# M707C.net
KiCad netlist of a schematic drawn in EAGLE
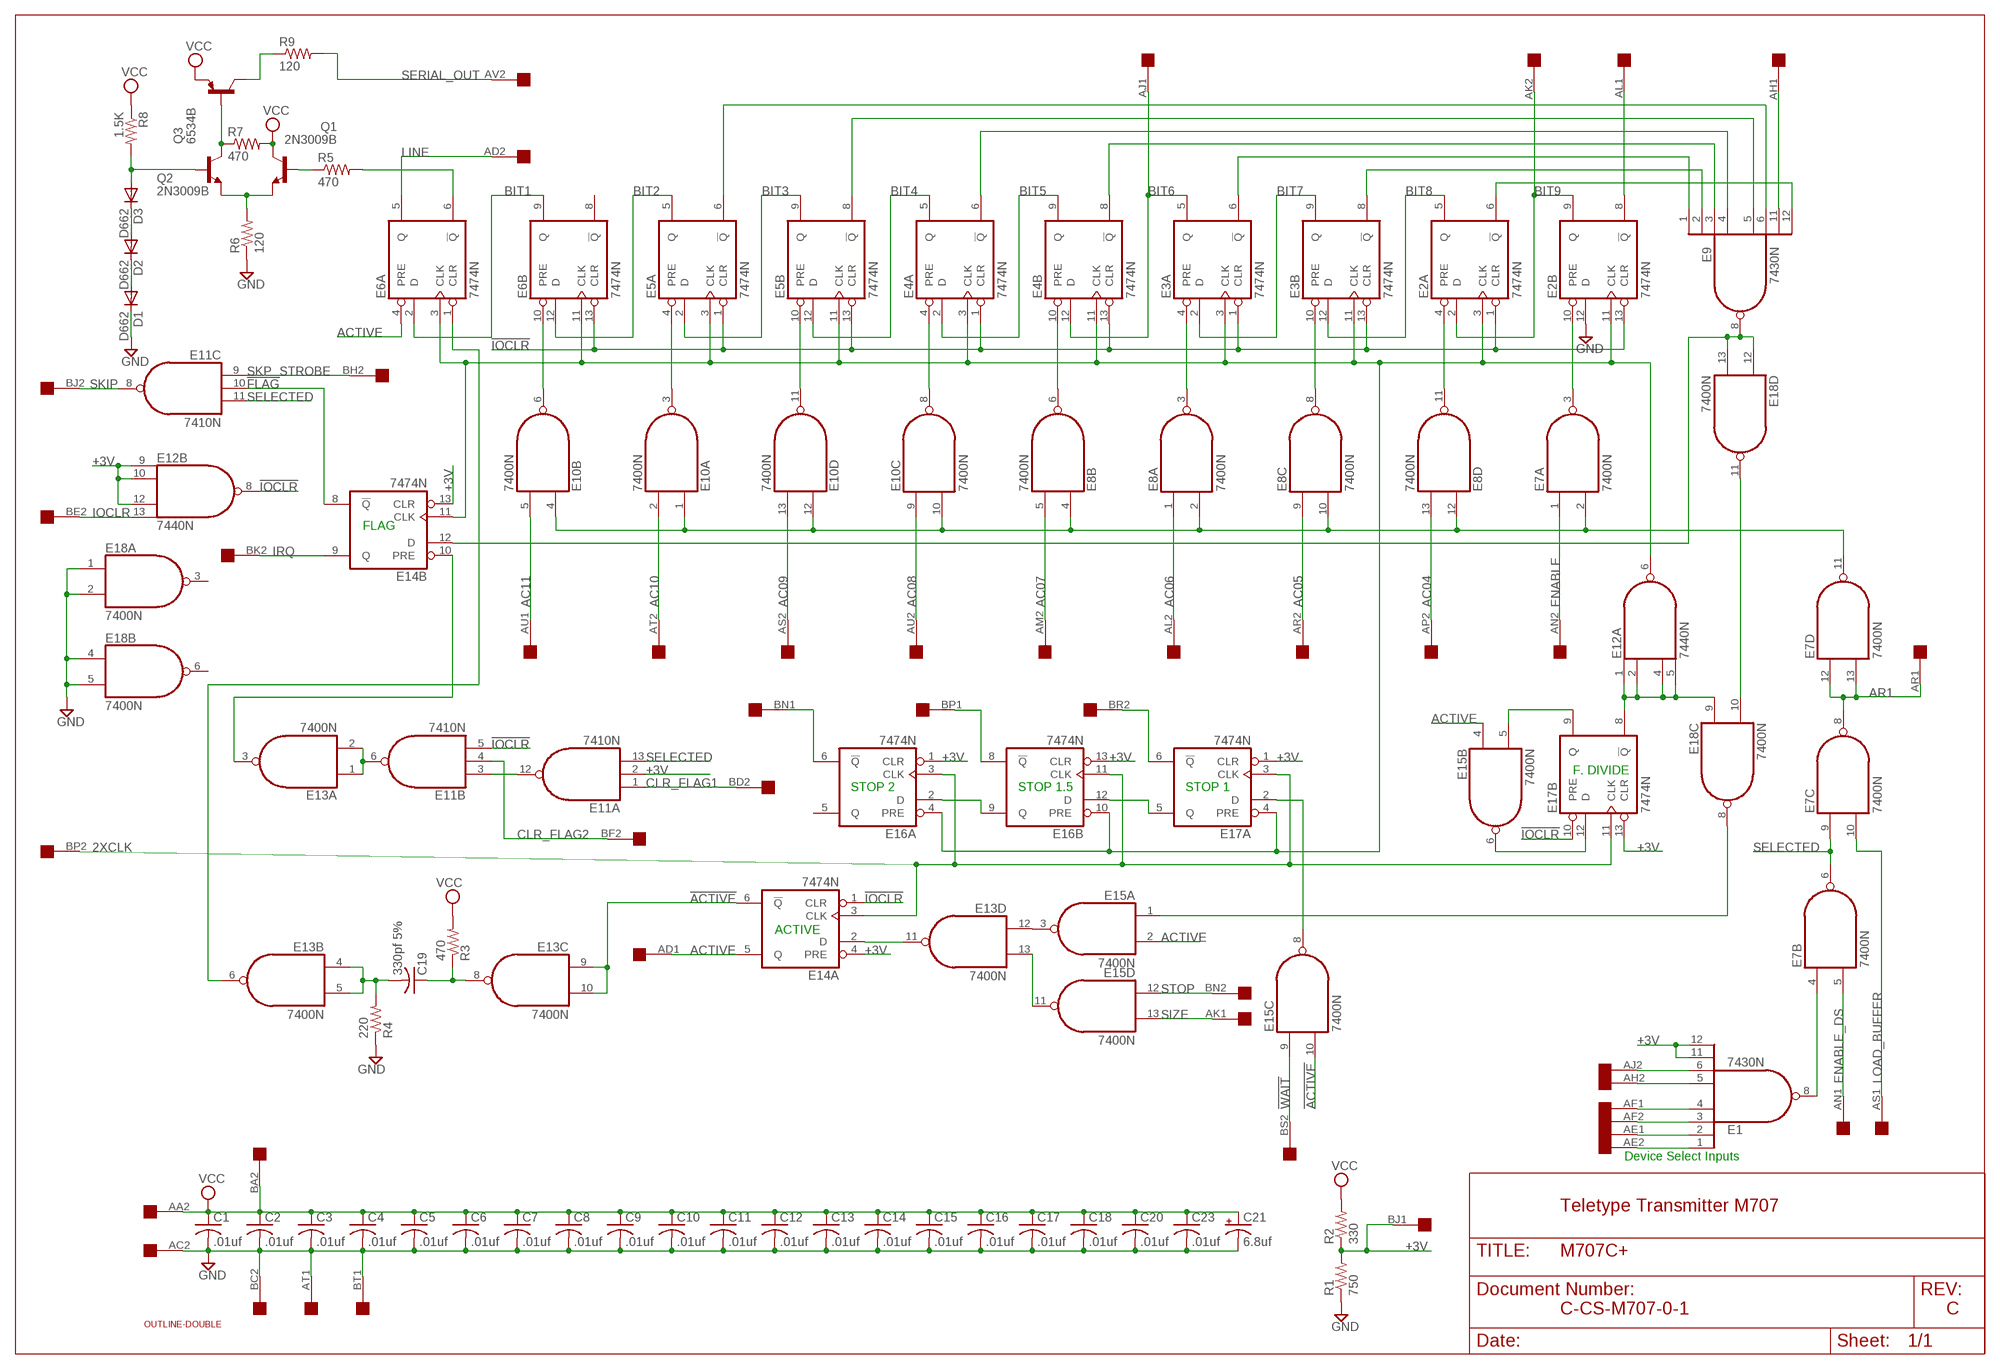
[diagram p0: schematic, sheet 1]

(export (version "E")
  (design (tool "Eeschema 10.0.6"))
  (components
    (comp (ref "C1")
      (value ".01uf")
      (footprint "eagle-import:C075-032X103")
      (libsource (lib "eagle-import") (part "C-US075-032X103"))
    )
    (comp (ref "C2")
      (value ".01uf")
      (footprint "eagle-import:C075-032X103")
      (libsource (lib "eagle-import") (part "C-US075-032X103"))
    )
    (comp (ref "C3")
      (value ".01uf")
      (footprint "eagle-import:C075-032X103")
      (libsource (lib "eagle-import") (part "C-US075-032X103"))
    )
    (comp (ref "C4")
      (value ".01uf")
      (footprint "eagle-import:C075-032X103")
      (libsource (lib "eagle-import") (part "C-US075-032X103"))
    )
    (comp (ref "C5")
      (value ".01uf")
      (footprint "eagle-import:C075-032X103")
      (libsource (lib "eagle-import") (part "C-US075-032X103"))
    )
    (comp (ref "C6")
      (value ".01uf")
      (footprint "eagle-import:C075-032X103")
      (libsource (lib "eagle-import") (part "C-US075-032X103"))
    )
    (comp (ref "C7")
      (value ".01uf")
      (footprint "eagle-import:C075-032X103")
      (libsource (lib "eagle-import") (part "C-US075-032X103"))
    )
    (comp (ref "C8")
      (value ".01uf")
      (footprint "eagle-import:C075-032X103")
      (libsource (lib "eagle-import") (part "C-US075-032X103"))
    )
    (comp (ref "C9")
      (value ".01uf")
      (footprint "eagle-import:C075-032X103")
      (libsource (lib "eagle-import") (part "C-US075-032X103"))
    )
    (comp (ref "C10")
      (value ".01uf")
      (footprint "eagle-import:C075-032X103")
      (libsource (lib "eagle-import") (part "C-US075-032X103"))
    )
    (comp (ref "C11")
      (value ".01uf")
      (footprint "eagle-import:C075-032X103")
      (libsource (lib "eagle-import") (part "C-US075-032X103"))
    )
    (comp (ref "C12")
      (value ".01uf")
      (footprint "eagle-import:C075-032X103")
      (libsource (lib "eagle-import") (part "C-US075-032X103"))
    )
    (comp (ref "C13")
      (value ".01uf")
      (footprint "eagle-import:C075-032X103")
      (libsource (lib "eagle-import") (part "C-US075-032X103"))
    )
    (comp (ref "C14")
      (value ".01uf")
      (footprint "eagle-import:C075-032X103")
      (libsource (lib "eagle-import") (part "C-US075-032X103"))
    )
    (comp (ref "C15")
      (value ".01uf")
      (footprint "eagle-import:C075-032X103")
      (libsource (lib "eagle-import") (part "C-US075-032X103"))
    )
    (comp (ref "C16")
      (value ".01uf")
      (footprint "eagle-import:C075-032X103")
      (libsource (lib "eagle-import") (part "C-US075-032X103"))
    )
    (comp (ref "C17")
      (value ".01uf")
      (footprint "eagle-import:C075-032X103")
      (libsource (lib "eagle-import") (part "C-US075-032X103"))
    )
    (comp (ref "C18")
      (value ".01uf")
      (footprint "eagle-import:C075-032X103")
      (libsource (lib "eagle-import") (part "C-US075-032X103"))
    )
    (comp (ref "C19")
      (value "330pf 5%")
      (footprint "eagle-import:C150-054X183")
      (libsource (lib "eagle-import") (part "C-US150-054X183"))
    )
    (comp (ref "C20")
      (value ".01uf")
      (footprint "eagle-import:C075-032X103")
      (libsource (lib "eagle-import") (part "C-US075-032X103"))
    )
    (comp (ref "C21")
      (value "6.8uf")
      (footprint "eagle-import:E15-5")
      (libsource (lib "eagle-import") (part "CPOL-USE15-5AXIAL"))
    )
    (comp (ref "C23")
      (value ".01uf")
      (footprint "eagle-import:C075-032X103")
      (libsource (lib "eagle-import") (part "C-US075-032X103"))
    )
    (comp (ref "D1")
      (value "D662")
      (footprint "eagle-import:SOD61B")
      (libsource (lib "eagle-import") (part "BY609"))
    )
    (comp (ref "D2")
      (value "D662")
      (footprint "eagle-import:SOD61B")
      (libsource (lib "eagle-import") (part "BY609"))
    )
    (comp (ref "D3")
      (value "D662")
      (footprint "eagle-import:SOD61B")
      (libsource (lib "eagle-import") (part "BY609"))
    )
    (comp (ref "E1")
      (value "7430N")
      (footprint "eagle-import:DIL14")
      (libsource (lib "eagle-import") (part "7430N"))
    )
    (comp (ref "E2")
      (value "7474N")
      (footprint "eagle-import:DIL14")
      (libsource (lib "eagle-import") (part "7474NS"))
    )
    (comp (ref "E3")
      (value "7474N")
      (footprint "eagle-import:DIL14")
      (libsource (lib "eagle-import") (part "7474NS"))
    )
    (comp (ref "E4")
      (value "7474N")
      (footprint "eagle-import:DIL14")
      (libsource (lib "eagle-import") (part "7474NS"))
    )
    (comp (ref "E5")
      (value "7474N")
      (footprint "eagle-import:DIL14")
      (libsource (lib "eagle-import") (part "7474NS"))
    )
    (comp (ref "E6")
      (value "7474N")
      (footprint "eagle-import:DIL14")
      (libsource (lib "eagle-import") (part "7474NS"))
    )
    (comp (ref "E7")
      (value "7400N")
      (footprint "eagle-import:DIL14")
      (libsource (lib "eagle-import") (part "7400N"))
    )
    (comp (ref "E8")
      (value "7400N")
      (footprint "eagle-import:DIL14")
      (libsource (lib "eagle-import") (part "7400N"))
    )
    (comp (ref "E9")
      (value "7430N")
      (footprint "eagle-import:DIL14")
      (libsource (lib "eagle-import") (part "7430N"))
    )
    (comp (ref "E10")
      (value "7400N")
      (footprint "eagle-import:DIL14")
      (libsource (lib "eagle-import") (part "7400N"))
    )
    (comp (ref "E11")
      (value "7410N")
      (footprint "eagle-import:DIL14")
      (libsource (lib "eagle-import") (part "7410N"))
    )
    (comp (ref "E12")
      (value "7440N")
      (footprint "eagle-import:DIL14")
      (libsource (lib "eagle-import") (part "7420NS"))
    )
    (comp (ref "E13")
      (value "7400N")
      (footprint "eagle-import:DIL14")
      (libsource (lib "eagle-import") (part "7400N"))
    )
    (comp (ref "E14")
      (value "7474N")
      (footprint "eagle-import:DIL14")
      (libsource (lib "eagle-import") (part "7474NS"))
    )
    (comp (ref "E15")
      (value "7400N")
      (footprint "eagle-import:DIL14")
      (libsource (lib "eagle-import") (part "7400N"))
    )
    (comp (ref "E16")
      (value "7474N")
      (footprint "eagle-import:DIL14")
      (libsource (lib "eagle-import") (part "7474NS"))
    )
    (comp (ref "E17")
      (value "7474N")
      (footprint "eagle-import:DIL14")
      (libsource (lib "eagle-import") (part "7474NS"))
    )
    (comp (ref "E18")
      (value "7400N")
      (footprint "eagle-import:DIL14")
      (libsource (lib "eagle-import") (part "7400N"))
    )
    (comp (ref "Q1")
      (value "2N3009B")
      (footprint "eagle-import:TO92-CBE")
      (libsource (lib "eagle-import") (part "-NPN-TO92-CBE2N4124"))
    )
    (comp (ref "Q2")
      (value "2N3009B")
      (footprint "eagle-import:TO92-CBE")
      (libsource (lib "eagle-import") (part "-NPN-TO92-CBE2N4124"))
    )
    (comp (ref "Q3")
      (value "6534B")
      (footprint "eagle-import:TO92-CBE")
      (libsource (lib "eagle-import") (part "-PNP-TO92-CBE2N4126"))
    )
    (comp (ref "R1")
      (value "750")
      (footprint "eagle-import:0207_15")
      (libsource (lib "eagle-import") (part "R-US_0207/15"))
    )
    (comp (ref "R2")
      (value "330")
      (footprint "eagle-import:0207_15")
      (libsource (lib "eagle-import") (part "R-US_0207/15"))
    )
    (comp (ref "R3")
      (value "470")
      (footprint "eagle-import:0207_10")
      (libsource (lib "eagle-import") (part "R-US_0207/10"))
    )
    (comp (ref "R4")
      (value "220")
      (footprint "eagle-import:0207_10")
      (libsource (lib "eagle-import") (part "R-US_0207/10"))
    )
    (comp (ref "R5")
      (value "470")
      (footprint "eagle-import:0207_10")
      (libsource (lib "eagle-import") (part "R-US_0207/10"))
    )
    (comp (ref "R6")
      (value "120")
      (footprint "eagle-import:0207_15")
      (libsource (lib "eagle-import") (part "R-US_0207/15"))
    )
    (comp (ref "R7")
      (value "470")
      (footprint "eagle-import:0207_10")
      (libsource (lib "eagle-import") (part "R-US_0207/10"))
    )
    (comp (ref "R8")
      (value "1.5K")
      (footprint "eagle-import:0207_15")
      (libsource (lib "eagle-import") (part "R-US_0207/15"))
    )
    (comp (ref "R9")
      (value "120")
      (footprint "eagle-import:0204_7")
      (libsource (lib "eagle-import") (part "R-US_0204/7"))
    )
    (comp (ref "U$1")
      (value "OUTLINE-DOUBLE")
      (footprint "eagle-import:DOUBLE")
      (libsource (lib "eagle-import") (part "OUTLINE-DOUBLE"))
    )
    (comp (ref "U$2")
      (value "DOUBLE")
      (footprint "eagle-import:EDGE-CON4")
      (libsource (lib "eagle-import") (part "DOUBLE"))
    )
  )
  (nets
    (net (code "1") (name "/+3V") (class "Default")
      (node (ref "E1") (pin "11") (pinfunction "I6_11") (pintype "input"))
      (node (ref "E1") (pin "12") (pinfunction "I7_12") (pintype "input"))
      (node (ref "E11") (pin "2") (pinfunction "I1_2") (pintype "input"))
      (node (ref "E12") (pin "10") (pinfunction "I1_10") (pintype "input"))
      (node (ref "E12") (pin "12") (pinfunction "I2_12") (pintype "input"))
      (node (ref "E12") (pin "9") (pinfunction "I0_9") (pintype "input"))
      (node (ref "E14") (pin "13") (pinfunction "CLR_13") (pintype "input"))
      (node (ref "E14") (pin "4") (pinfunction "PRE_4") (pintype "input"))
      (node (ref "E16") (pin "1") (pinfunction "CLR_1") (pintype "input"))
      (node (ref "E16") (pin "13") (pinfunction "CLR_13") (pintype "input"))
      (node (ref "E17") (pin "1") (pinfunction "CLR_1") (pintype "input"))
      (node (ref "E17") (pin "13") (pinfunction "CLR_13") (pintype "input"))
      (node (ref "R1") (pin "2") (pinfunction "2_2") (pintype "passive"))
      (node (ref "R2") (pin "1") (pinfunction "1_1") (pintype "passive"))
      (node (ref "U$2") (pin "BJ1") (pinfunction "1_BJ1") (pintype "bidirectional"))
    )
    (net (code "2") (name "/2XCLK") (class "Default")
      (node (ref "E14") (pin "3") (pinfunction "CLK_3") (pintype "input"))
      (node (ref "E16") (pin "11") (pinfunction "CLK_11") (pintype "input"))
      (node (ref "E16") (pin "3") (pinfunction "CLK_3") (pintype "input"))
      (node (ref "E17") (pin "11") (pinfunction "CLK_11") (pintype "input"))
      (node (ref "E17") (pin "3") (pinfunction "CLK_3") (pintype "input"))
      (node (ref "U$2") (pin "BP2") (pinfunction "1_BP2") (pintype "bidirectional"))
    )
    (net (code "3") (name "/AC04") (class "Default")
      (node (ref "E8") (pin "13") (pinfunction "I1_13") (pintype "input"))
      (node (ref "U$2") (pin "AP2") (pinfunction "1_AP2") (pintype "bidirectional"))
    )
    (net (code "4") (name "/AC05") (class "Default")
      (node (ref "E8") (pin "9") (pinfunction "I0_9") (pintype "input"))
      (node (ref "U$2") (pin "AR2") (pinfunction "1_AR2") (pintype "bidirectional"))
    )
    (net (code "5") (name "/AC06") (class "Default")
      (node (ref "E8") (pin "1") (pinfunction "I0_1") (pintype "input"))
      (node (ref "U$2") (pin "AL2") (pinfunction "1_AL2") (pintype "bidirectional"))
    )
    (net (code "6") (name "/AC07") (class "Default")
      (node (ref "E8") (pin "5") (pinfunction "I1_5") (pintype "input"))
      (node (ref "U$2") (pin "AM2") (pinfunction "1_AM2") (pintype "bidirectional"))
    )
    (net (code "7") (name "/AC08") (class "Default")
      (node (ref "E10") (pin "9") (pinfunction "I0_9") (pintype "input"))
      (node (ref "U$2") (pin "AU2") (pinfunction "1_AU2") (pintype "bidirectional"))
    )
    (net (code "8") (name "/AC09") (class "Default")
      (node (ref "E10") (pin "13") (pinfunction "I1_13") (pintype "input"))
      (node (ref "U$2") (pin "AS2") (pinfunction "1_AS2") (pintype "bidirectional"))
    )
    (net (code "9") (name "/AC10") (class "Default")
      (node (ref "E10") (pin "2") (pinfunction "I1_2") (pintype "input"))
      (node (ref "U$2") (pin "AT2") (pinfunction "1_AT2") (pintype "bidirectional"))
    )
    (net (code "10") (name "/AC11") (class "Default")
      (node (ref "E10") (pin "5") (pinfunction "I1_5") (pintype "input"))
      (node (ref "U$2") (pin "AU1") (pinfunction "1_AU1") (pintype "bidirectional"))
    )
    (net (code "11") (name "/ACTIVE") (class "Default")
      (node (ref "E14") (pin "5") (pinfunction "Q_5") (pintype "output"))
      (node (ref "E15") (pin "2") (pinfunction "I1_2") (pintype "input"))
      (node (ref "E15") (pin "4") (pinfunction "I0_4") (pintype "input"))
      (node (ref "E6") (pin "4") (pinfunction "PRE_4") (pintype "input"))
      (node (ref "U$2") (pin "AD1") (pinfunction "1_AD1") (pintype "bidirectional"))
    )
    (net (code "12") (name "/AR1") (class "Default")
      (node (ref "E7") (pin "12") (pinfunction "I0_12") (pintype "input"))
      (node (ref "E7") (pin "13") (pinfunction "I1_13") (pintype "input"))
      (node (ref "E7") (pin "8") (pinfunction "O_8") (pintype "output"))
      (node (ref "U$2") (pin "AR1") (pinfunction "1_AR1") (pintype "bidirectional"))
    )
    (net (code "13") (name "/BIT1") (class "Default")
      (node (ref "E6") (pin "2") (pinfunction "D_2") (pintype "input"))
      (node (ref "E6") (pin "9") (pinfunction "Q_9") (pintype "output"))
    )
    (net (code "14") (name "/BIT2") (class "Default")
      (node (ref "E5") (pin "5") (pinfunction "Q_5") (pintype "output"))
      (node (ref "E6") (pin "12") (pinfunction "D_12") (pintype "input"))
    )
    (net (code "15") (name "/BIT3") (class "Default")
      (node (ref "E5") (pin "2") (pinfunction "D_2") (pintype "input"))
      (node (ref "E5") (pin "9") (pinfunction "Q_9") (pintype "output"))
    )
    (net (code "16") (name "/BIT4") (class "Default")
      (node (ref "E4") (pin "5") (pinfunction "Q_5") (pintype "output"))
      (node (ref "E5") (pin "12") (pinfunction "D_12") (pintype "input"))
    )
    (net (code "17") (name "/BIT5") (class "Default")
      (node (ref "E4") (pin "2") (pinfunction "D_2") (pintype "input"))
      (node (ref "E4") (pin "9") (pinfunction "Q_9") (pintype "output"))
    )
    (net (code "18") (name "/BIT6") (class "Default")
      (node (ref "E3") (pin "5") (pinfunction "Q_5") (pintype "output"))
      (node (ref "E4") (pin "12") (pinfunction "D_12") (pintype "input"))
      (node (ref "U$2") (pin "AJ1") (pinfunction "1_AJ1") (pintype "bidirectional"))
    )
    (net (code "19") (name "/BIT7") (class "Default")
      (node (ref "E3") (pin "2") (pinfunction "D_2") (pintype "input"))
      (node (ref "E3") (pin "9") (pinfunction "Q_9") (pintype "output"))
    )
    (net (code "20") (name "/BIT8") (class "Default")
      (node (ref "E2") (pin "5") (pinfunction "Q_5") (pintype "output"))
      (node (ref "E3") (pin "12") (pinfunction "D_12") (pintype "input"))
    )
    (net (code "21") (name "/BIT9") (class "Default")
      (node (ref "E2") (pin "2") (pinfunction "D_2") (pintype "input"))
      (node (ref "E2") (pin "9") (pinfunction "Q_9") (pintype "output"))
      (node (ref "U$2") (pin "AK2") (pinfunction "1_AK2") (pintype "bidirectional"))
    )
    (net (code "22") (name "/CLR_FLAG1") (class "Default")
      (node (ref "E11") (pin "1") (pinfunction "I0_1") (pintype "input"))
      (node (ref "U$2") (pin "BD2") (pinfunction "1_BD2") (pintype "bidirectional"))
    )
    (net (code "23") (name "/CLR_FLAG2") (class "Default")
      (node (ref "E11") (pin "4") (pinfunction "I1_4") (pintype "input"))
      (node (ref "U$2") (pin "BF2") (pinfunction "1_BF2") (pintype "bidirectional"))
    )
    (net (code "24") (name "/ENABLE") (class "Default")
      (node (ref "E7") (pin "1") (pinfunction "I0_1") (pintype "input"))
      (node (ref "U$2") (pin "AN2") (pinfunction "1_AN2") (pintype "bidirectional"))
    )
    (net (code "25") (name "/ENABLE_DS") (class "Default")
      (node (ref "E7") (pin "5") (pinfunction "I1_5") (pintype "input"))
      (node (ref "U$2") (pin "AN1") (pinfunction "1_AN1") (pintype "bidirectional"))
    )
    (net (code "26") (name "/IOCLR") (class "Default")
      (node (ref "E12") (pin "13") (pinfunction "I3_13") (pintype "input"))
      (node (ref "U$2") (pin "BE2") (pinfunction "1_BE2") (pintype "bidirectional"))
    )
    (net (code "27") (name "/IRQ") (class "Default")
      (node (ref "E14") (pin "9") (pinfunction "Q_9") (pintype "output"))
      (node (ref "U$2") (pin "BK2") (pinfunction "1_BK2") (pintype "bidirectional"))
    )
    (net (code "28") (name "/LINE") (class "Default")
      (node (ref "E6") (pin "5") (pinfunction "Q_5") (pintype "output"))
      (node (ref "U$2") (pin "AD2") (pinfunction "1_AD2") (pintype "bidirectional"))
    )
    (net (code "29") (name "/LOAD_BUFFER") (class "Default")
      (node (ref "E7") (pin "10") (pinfunction "I1_10") (pintype "input"))
      (node (ref "U$2") (pin "AS1") (pinfunction "1_AS1") (pintype "bidirectional"))
    )
    (net (code "30") (name "/SELECTED") (class "Default")
      (node (ref "E11") (pin "11") (pinfunction "I2_11") (pintype "input"))
      (node (ref "E11") (pin "13") (pinfunction "I2_13") (pintype "input"))
      (node (ref "E7") (pin "6") (pinfunction "O_6") (pintype "output"))
      (node (ref "E7") (pin "9") (pinfunction "I0_9") (pintype "input"))
    )
    (net (code "31") (name "/SERIAL_OUT") (class "Default")
      (node (ref "R9") (pin "2") (pinfunction "2_2") (pintype "passive"))
      (node (ref "U$2") (pin "AV2") (pinfunction "1_AV2") (pintype "bidirectional"))
    )
    (net (code "32") (name "/SIZE") (class "Default")
      (node (ref "E15") (pin "13") (pinfunction "I1_13") (pintype "input"))
      (node (ref "U$2") (pin "AK1") (pinfunction "1_AK1") (pintype "bidirectional"))
    )
    (net (code "33") (name "/SKIP") (class "Default")
      (node (ref "E11") (pin "8") (pinfunction "O_8") (pintype "output"))
      (node (ref "U$2") (pin "BJ2") (pinfunction "1_BJ2") (pintype "bidirectional"))
    )
    (net (code "34") (name "/SKP_STROBE") (class "Default")
      (node (ref "E11") (pin "9") (pinfunction "I0_9") (pintype "input"))
      (node (ref "U$2") (pin "BH2") (pinfunction "1_BH2") (pintype "bidirectional"))
    )
    (net (code "35") (name "/STOP") (class "Default")
      (node (ref "E15") (pin "12") (pinfunction "I0_12") (pintype "input"))
      (node (ref "U$2") (pin "BN2") (pinfunction "1_BN2") (pintype "bidirectional"))
    )
    (net (code "36") (name "/~{ACTIVE}") (class "Default")
      (node (ref "E13") (pin "10") (pinfunction "I1_10") (pintype "input"))
      (node (ref "E13") (pin "9") (pinfunction "I0_9") (pintype "input"))
      (node (ref "E14") (pin "6") (pinfunction "~{Q}_6") (pintype "output"))
      (node (ref "E15") (pin "10") (pinfunction "I1_10") (pintype "input"))
    )
    (net (code "37") (name "/~{FLAG}") (class "Default")
      (node (ref "E11") (pin "10") (pinfunction "I1_10") (pintype "input"))
      (node (ref "E14") (pin "8") (pinfunction "~{Q}_8") (pintype "output"))
    )
    (net (code "38") (name "/~{IOCLR}") (class "Default")
      (node (ref "E11") (pin "5") (pinfunction "I2_5") (pintype "input"))
      (node (ref "E12") (pin "8") (pinfunction "O_8") (pintype "output"))
      (node (ref "E14") (pin "1") (pinfunction "CLR_1") (pintype "input"))
      (node (ref "E17") (pin "10") (pinfunction "PRE_10") (pintype "input"))
      (node (ref "E2") (pin "1") (pinfunction "CLR_1") (pintype "input"))
      (node (ref "E2") (pin "13") (pinfunction "CLR_13") (pintype "input"))
      (node (ref "E3") (pin "1") (pinfunction "CLR_1") (pintype "input"))
      (node (ref "E3") (pin "13") (pinfunction "CLR_13") (pintype "input"))
      (node (ref "E4") (pin "1") (pinfunction "CLR_1") (pintype "input"))
      (node (ref "E4") (pin "13") (pinfunction "CLR_13") (pintype "input"))
      (node (ref "E5") (pin "1") (pinfunction "CLR_1") (pintype "input"))
      (node (ref "E5") (pin "13") (pinfunction "CLR_13") (pintype "input"))
      (node (ref "E6") (pin "13") (pinfunction "CLR_13") (pintype "input"))
    )
    (net (code "39") (name "/~{WAIT}") (class "Default")
      (node (ref "E15") (pin "9") (pinfunction "I0_9") (pintype "input"))
      (node (ref "U$2") (pin "BS2") (pinfunction "1_BS2") (pintype "bidirectional"))
    )
    (net (code "40") (name "GND") (class "Default")
      (node (ref "C1") (pin "2") (pinfunction "2_2") (pintype "passive"))
      (node (ref "C10") (pin "2") (pinfunction "2_2") (pintype "passive"))
      (node (ref "C11") (pin "2") (pinfunction "2_2") (pintype "passive"))
      (node (ref "C12") (pin "2") (pinfunction "2_2") (pintype "passive"))
      (node (ref "C13") (pin "2") (pinfunction "2_2") (pintype "passive"))
      (node (ref "C14") (pin "2") (pinfunction "2_2") (pintype "passive"))
      (node (ref "C15") (pin "2") (pinfunction "2_2") (pintype "passive"))
      (node (ref "C16") (pin "2") (pinfunction "2_2") (pintype "passive"))
      (node (ref "C17") (pin "2") (pinfunction "2_2") (pintype "passive"))
      (node (ref "C18") (pin "2") (pinfunction "2_2") (pintype "passive"))
      (node (ref "C2") (pin "2") (pinfunction "2_2") (pintype "passive"))
      (node (ref "C20") (pin "2") (pinfunction "2_2") (pintype "passive"))
      (node (ref "C21") (pin "-") (pinfunction "-_-") (pintype "passive"))
      (node (ref "C23") (pin "2") (pinfunction "2_2") (pintype "passive"))
      (node (ref "C3") (pin "2") (pinfunction "2_2") (pintype "passive"))
      (node (ref "C4") (pin "2") (pinfunction "2_2") (pintype "passive"))
      (node (ref "C5") (pin "2") (pinfunction "2_2") (pintype "passive"))
      (node (ref "C6") (pin "2") (pinfunction "2_2") (pintype "passive"))
      (node (ref "C7") (pin "2") (pinfunction "2_2") (pintype "passive"))
      (node (ref "C8") (pin "2") (pinfunction "2_2") (pintype "passive"))
      (node (ref "C9") (pin "2") (pinfunction "2_2") (pintype "passive"))
      (node (ref "D1") (pin "C") (pinfunction "C_C") (pintype "passive"))
      (node (ref "E18") (pin "1") (pinfunction "I0_1") (pintype "input"))
      (node (ref "E18") (pin "2") (pinfunction "I1_2") (pintype "input"))
      (node (ref "E18") (pin "4") (pinfunction "I0_4") (pintype "input"))
      (node (ref "E18") (pin "5") (pinfunction "I1_5") (pintype "input"))
      (node (ref "E2") (pin "12") (pinfunction "D_12") (pintype "input"))
      (node (ref "R1") (pin "1") (pinfunction "1_1") (pintype "passive"))
      (node (ref "R4") (pin "1") (pinfunction "1_1") (pintype "passive"))
      (node (ref "R6") (pin "1") (pinfunction "1_1") (pintype "passive"))
      (node (ref "U$2") (pin "AC2") (pinfunction "1_AC2") (pintype "bidirectional"))
      (node (ref "U$2") (pin "AT1") (pinfunction "1_AT1") (pintype "bidirectional"))
      (node (ref "U$2") (pin "BC2") (pinfunction "1_BC2") (pintype "bidirectional"))
      (node (ref "U$2") (pin "BT1") (pinfunction "1_BT1") (pintype "bidirectional"))
    )
    (net (code "41") (name "Net-(D1-PadA)") (class "Default")
      (node (ref "D1") (pin "A") (pinfunction "A_A") (pintype "passive"))
      (node (ref "D2") (pin "C") (pinfunction "C_C") (pintype "passive"))
    )
    (net (code "42") (name "Net-(D2-PadA)") (class "Default")
      (node (ref "D2") (pin "A") (pinfunction "A_A") (pintype "passive"))
      (node (ref "D3") (pin "C") (pinfunction "C_C") (pintype "passive"))
    )
    (net (code "43") (name "Net-(D3-PadA)") (class "Default")
      (node (ref "D3") (pin "A") (pinfunction "A_A") (pintype "passive"))
      (node (ref "Q2") (pin "B") (pinfunction "B_B") (pintype "passive"))
      (node (ref "R8") (pin "2") (pinfunction "2_2") (pintype "passive"))
    )
    (net (code "44") (name "Net-(E1A-I0)") (class "Default")
      (node (ref "E1") (pin "1") (pinfunction "I0_1") (pintype "input"))
      (node (ref "U$2") (pin "AE2") (pinfunction "1_AE2") (pintype "bidirectional"))
    )
    (net (code "45") (name "Net-(E1A-I1)") (class "Default")
      (node (ref "E1") (pin "2") (pinfunction "I1_2") (pintype "input"))
      (node (ref "U$2") (pin "AE1") (pinfunction "1_AE1") (pintype "bidirectional"))
    )
    (net (code "46") (name "Net-(E1A-I2)") (class "Default")
      (node (ref "E1") (pin "3") (pinfunction "I2_3") (pintype "input"))
      (node (ref "U$2") (pin "AF2") (pinfunction "1_AF2") (pintype "bidirectional"))
    )
    (net (code "47") (name "Net-(E1A-I3)") (class "Default")
      (node (ref "E1") (pin "4") (pinfunction "I3_4") (pintype "input"))
      (node (ref "U$2") (pin "AF1") (pinfunction "1_AF1") (pintype "bidirectional"))
    )
    (net (code "48") (name "Net-(E1A-I4)") (class "Default")
      (node (ref "E1") (pin "5") (pinfunction "I4_5") (pintype "input"))
      (node (ref "U$2") (pin "AH2") (pinfunction "1_AH2") (pintype "bidirectional"))
    )
    (net (code "49") (name "Net-(E1A-I5)") (class "Default")
      (node (ref "E1") (pin "6") (pinfunction "I5_6") (pintype "input"))
      (node (ref "U$2") (pin "AJ2") (pinfunction "1_AJ2") (pintype "bidirectional"))
    )
    (net (code "50") (name "Net-(E1A-O)") (class "Default")
      (node (ref "E1") (pin "8") (pinfunction "O_8") (pintype "output"))
      (node (ref "E7") (pin "4") (pinfunction "I0_4") (pintype "input"))
    )
    (net (code "51") (name "Net-(E2A-PRE)") (class "Default")
      (node (ref "E2") (pin "4") (pinfunction "PRE_4") (pintype "input"))
      (node (ref "E8") (pin "11") (pinfunction "O_11") (pintype "output"))
    )
    (net (code "52") (name "Net-(E2A-~{Q})") (class "Default")
      (node (ref "E2") (pin "6") (pinfunction "~{Q}_6") (pintype "output"))
      (node (ref "E9") (pin "12") (pinfunction "I7_12") (pintype "input"))
    )
    (net (code "53") (name "Net-(E2B-PRE)") (class "Default")
      (node (ref "E2") (pin "10") (pinfunction "PRE_10") (pintype "input"))
      (node (ref "E7") (pin "3") (pinfunction "O_3") (pintype "output"))
    )
    (net (code "54") (name "Net-(E2B-~{Q})") (class "Default")
      (node (ref "E2") (pin "8") (pinfunction "~{Q}_8") (pintype "output"))
      (node (ref "U$2") (pin "AL1") (pinfunction "1_AL1") (pintype "bidirectional"))
    )
    (net (code "55") (name "Net-(E3A-PRE)") (class "Default")
      (node (ref "E3") (pin "4") (pinfunction "PRE_4") (pintype "input"))
      (node (ref "E8") (pin "3") (pinfunction "O_3") (pintype "output"))
    )
    (net (code "56") (name "Net-(E3A-~{Q})") (class "Default")
      (node (ref "E3") (pin "6") (pinfunction "~{Q}_6") (pintype "output"))
      (node (ref "E9") (pin "1") (pinfunction "I0_1") (pintype "input"))
    )
    (net (code "57") (name "Net-(E3B-PRE)") (class "Default")
      (node (ref "E3") (pin "10") (pinfunction "PRE_10") (pintype "input"))
      (node (ref "E8") (pin "8") (pinfunction "O_8") (pintype "output"))
    )
    (net (code "58") (name "Net-(E3B-~{Q})") (class "Default")
      (node (ref "E3") (pin "8") (pinfunction "~{Q}_8") (pintype "output"))
      (node (ref "E9") (pin "2") (pinfunction "I1_2") (pintype "input"))
    )
    (net (code "59") (name "Net-(E4A-~{Q})") (class "Default")
      (node (ref "E4") (pin "6") (pinfunction "~{Q}_6") (pintype "output"))
      (node (ref "E9") (pin "4") (pinfunction "I3_4") (pintype "input"))
    )
    (net (code "60") (name "Net-(E4B-PRE)") (class "Default")
      (node (ref "E4") (pin "10") (pinfunction "PRE_10") (pintype "input"))
      (node (ref "E8") (pin "6") (pinfunction "O_6") (pintype "output"))
    )
    (net (code "61") (name "Net-(E4B-~{Q})") (class "Default")
      (node (ref "E4") (pin "8") (pinfunction "~{Q}_8") (pintype "output"))
      (node (ref "E9") (pin "3") (pinfunction "I2_3") (pintype "input"))
    )
    (net (code "62") (name "Net-(E5A-~{Q})") (class "Default")
      (node (ref "E5") (pin "6") (pinfunction "~{Q}_6") (pintype "output"))
      (node (ref "E9") (pin "6") (pinfunction "I5_6") (pintype "input"))
    )
    (net (code "63") (name "Net-(E5B-~{Q})") (class "Default")
      (node (ref "E5") (pin "8") (pinfunction "~{Q}_8") (pintype "output"))
      (node (ref "E9") (pin "5") (pinfunction "I4_5") (pintype "input"))
    )
    (net (code "64") (name "Net-(E6A-~{Q})") (class "Default")
      (node (ref "E6") (pin "6") (pinfunction "~{Q}_6") (pintype "output"))
      (node (ref "R5") (pin "2") (pinfunction "2_2") (pintype "passive"))
    )
    (net (code "65") (name "Net-(E9A-I6)") (class "Default")
      (node (ref "E9") (pin "11") (pinfunction "I6_11") (pintype "input"))
      (node (ref "U$2") (pin "AH1") (pinfunction "1_AH1") (pintype "bidirectional"))
    )
    (net (code "66") (name "Net-(E10A-I0)") (class "Default")
      (node (ref "E10") (pin "1") (pinfunction "I0_1") (pintype "input"))
      (node (ref "E10") (pin "10") (pinfunction "I1_10") (pintype "input"))
      (node (ref "E10") (pin "12") (pinfunction "I0_12") (pintype "input"))
      (node (ref "E10") (pin "4") (pinfunction "I0_4") (pintype "input"))
      (node (ref "E7") (pin "11") (pinfunction "O_11") (pintype "output"))
      (node (ref "E7") (pin "2") (pinfunction "I1_2") (pintype "input"))
      (node (ref "E8") (pin "10") (pinfunction "I1_10") (pintype "input"))
      (node (ref "E8") (pin "12") (pinfunction "I0_12") (pintype "input"))
      (node (ref "E8") (pin "2") (pinfunction "I1_2") (pintype "input"))
      (node (ref "E8") (pin "4") (pinfunction "I0_4") (pintype "input"))
    )
    (net (code "67") (name "Net-(E10A-O)") (class "Default")
      (node (ref "E10") (pin "3") (pinfunction "O_3") (pintype "output"))
      (node (ref "E5") (pin "4") (pinfunction "PRE_4") (pintype "input"))
    )
    (net (code "68") (name "Net-(E10B-O)") (class "Default")
      (node (ref "E10") (pin "6") (pinfunction "O_6") (pintype "output"))
      (node (ref "E6") (pin "10") (pinfunction "PRE_10") (pintype "input"))
    )
    (net (code "69") (name "Net-(E10C-O)") (class "Default")
      (node (ref "E10") (pin "8") (pinfunction "O_8") (pintype "output"))
      (node (ref "E4") (pin "4") (pinfunction "PRE_4") (pintype "input"))
    )
    (net (code "70") (name "Net-(E10D-O)") (class "Default")
      (node (ref "E10") (pin "11") (pinfunction "O_11") (pintype "output"))
      (node (ref "E5") (pin "10") (pinfunction "PRE_10") (pintype "input"))
    )
    (net (code "71") (name "Net-(E11A-O)") (class "Default")
      (node (ref "E11") (pin "12") (pinfunction "O_12") (pintype "output"))
      (node (ref "E11") (pin "3") (pinfunction "I0_3") (pintype "input"))
    )
    (net (code "72") (name "Net-(E11B-O)") (class "Default")
      (node (ref "E11") (pin "6") (pinfunction "O_6") (pintype "output"))
      (node (ref "E13") (pin "1") (pinfunction "I0_1") (pintype "input"))
      (node (ref "E13") (pin "2") (pinfunction "I1_2") (pintype "input"))
    )
    (net (code "73") (name "Net-(E12A-I0)") (class "Default")
      (node (ref "E12") (pin "1") (pinfunction "I0_1") (pintype "input"))
      (node (ref "E12") (pin "2") (pinfunction "I1_2") (pintype "input"))
      (node (ref "E12") (pin "4") (pinfunction "I2_4") (pintype "input"))
      (node (ref "E12") (pin "5") (pinfunction "I3_5") (pintype "input"))
      (node (ref "E17") (pin "8") (pinfunction "~{Q}_8") (pintype "output"))
      (node (ref "E18") (pin "9") (pinfunction "I0_9") (pintype "input"))
    )
    (net (code "74") (name "Net-(E12A-O)") (class "Default")
      (node (ref "E12") (pin "6") (pinfunction "O_6") (pintype "output"))
      (node (ref "E14") (pin "11") (pinfunction "CLK_11") (pintype "input"))
      (node (ref "E16") (pin "10") (pinfunction "PRE_10") (pintype "input"))
      (node (ref "E16") (pin "4") (pinfunction "PRE_4") (pintype "input"))
      (node (ref "E17") (pin "4") (pinfunction "PRE_4") (pintype "input"))
      (node (ref "E2") (pin "11") (pinfunction "CLK_11") (pintype "input"))
      (node (ref "E2") (pin "3") (pinfunction "CLK_3") (pintype "input"))
      (node (ref "E3") (pin "11") (pinfunction "CLK_11") (pintype "input"))
      (node (ref "E3") (pin "3") (pinfunction "CLK_3") (pintype "input"))
      (node (ref "E4") (pin "11") (pinfunction "CLK_11") (pintype "input"))
      (node (ref "E4") (pin "3") (pinfunction "CLK_3") (pintype "input"))
      (node (ref "E5") (pin "11") (pinfunction "CLK_11") (pintype "input"))
      (node (ref "E5") (pin "3") (pinfunction "CLK_3") (pintype "input"))
      (node (ref "E6") (pin "11") (pinfunction "CLK_11") (pintype "input"))
      (node (ref "E6") (pin "3") (pinfunction "CLK_3") (pintype "input"))
    )
    (net (code "75") (name "Net-(E13A-O)") (class "Default")
      (node (ref "E13") (pin "3") (pinfunction "O_3") (pintype "output"))
      (node (ref "E14") (pin "10") (pinfunction "PRE_10") (pintype "input"))
    )
    (net (code "76") (name "Net-(E13B-I0)") (class "Default")
      (node (ref "C19") (pin "2") (pinfunction "2_2") (pintype "passive"))
      (node (ref "E13") (pin "4") (pinfunction "I0_4") (pintype "input"))
      (node (ref "E13") (pin "5") (pinfunction "I1_5") (pintype "input"))
      (node (ref "R4") (pin "2") (pinfunction "2_2") (pintype "passive"))
    )
    (net (code "77") (name "Net-(E13B-O)") (class "Default")
      (node (ref "E13") (pin "6") (pinfunction "O_6") (pintype "output"))
      (node (ref "E6") (pin "1") (pinfunction "CLR_1") (pintype "input"))
    )
    (net (code "78") (name "Net-(E13C-O)") (class "Default")
      (node (ref "C19") (pin "1") (pinfunction "1_1") (pintype "passive"))
      (node (ref "E13") (pin "8") (pinfunction "O_8") (pintype "output"))
      (node (ref "R3") (pin "1") (pinfunction "1_1") (pintype "passive"))
    )
    (net (code "79") (name "Net-(E13D-I0)") (class "Default")
      (node (ref "E13") (pin "12") (pinfunction "I0_12") (pintype "input"))
      (node (ref "E15") (pin "3") (pinfunction "O_3") (pintype "output"))
    )
    (net (code "80") (name "Net-(E13D-I1)") (class "Default")
      (node (ref "E13") (pin "13") (pinfunction "I1_13") (pintype "input"))
      (node (ref "E15") (pin "11") (pinfunction "O_11") (pintype "output"))
    )
    (net (code "81") (name "Net-(E13D-O)") (class "Default")
      (node (ref "E13") (pin "11") (pinfunction "O_11") (pintype "output"))
      (node (ref "E14") (pin "2") (pinfunction "D_2") (pintype "input"))
    )
    (net (code "82") (name "Net-(E14B-D)") (class "Default")
      (node (ref "E14") (pin "12") (pinfunction "D_12") (pintype "input"))
      (node (ref "E18") (pin "12") (pinfunction "I0_12") (pintype "input"))
      (node (ref "E18") (pin "13") (pinfunction "I1_13") (pintype "input"))
      (node (ref "E9") (pin "8") (pinfunction "O_8") (pintype "output"))
    )
    (net (code "83") (name "Net-(E15A-I0)") (class "Default")
      (node (ref "E15") (pin "1") (pinfunction "I0_1") (pintype "input"))
      (node (ref "E18") (pin "8") (pinfunction "O_8") (pintype "output"))
    )
    (net (code "84") (name "Net-(E15B-I1)") (class "Default")
      (node (ref "E15") (pin "5") (pinfunction "I1_5") (pintype "input"))
      (node (ref "E17") (pin "9") (pinfunction "Q_9") (pintype "output"))
    )
    (net (code "85") (name "Net-(E15B-O)") (class "Default")
      (node (ref "E15") (pin "6") (pinfunction "O_6") (pintype "output"))
      (node (ref "E17") (pin "12") (pinfunction "D_12") (pintype "input"))
    )
    (net (code "86") (name "Net-(E15C-O)") (class "Default")
      (node (ref "E15") (pin "8") (pinfunction "O_8") (pintype "output"))
      (node (ref "E17") (pin "2") (pinfunction "D_2") (pintype "input"))
    )
    (net (code "87") (name "Net-(E16A-D)") (class "Default")
      (node (ref "E16") (pin "2") (pinfunction "D_2") (pintype "input"))
      (node (ref "E16") (pin "9") (pinfunction "Q_9") (pintype "output"))
    )
    (net (code "88") (name "Net-(E16A-~{Q})") (class "Default")
      (node (ref "E16") (pin "6") (pinfunction "~{Q}_6") (pintype "output"))
      (node (ref "U$2") (pin "BN1") (pinfunction "1_BN1") (pintype "bidirectional"))
    )
    (net (code "89") (name "Net-(E16B-D)") (class "Default")
      (node (ref "E16") (pin "12") (pinfunction "D_12") (pintype "input"))
      (node (ref "E17") (pin "5") (pinfunction "Q_5") (pintype "output"))
    )
    (net (code "90") (name "Net-(E16B-~{Q})") (class "Default")
      (node (ref "E16") (pin "8") (pinfunction "~{Q}_8") (pintype "output"))
      (node (ref "U$2") (pin "BP1") (pinfunction "1_BP1") (pintype "bidirectional"))
    )
    (net (code "91") (name "Net-(E17A-~{Q})") (class "Default")
      (node (ref "E17") (pin "6") (pinfunction "~{Q}_6") (pintype "output"))
      (node (ref "U$2") (pin "BR2") (pinfunction "1_BR2") (pintype "bidirectional"))
    )
    (net (code "92") (name "Net-(E18C-I1)") (class "Default")
      (node (ref "E18") (pin "10") (pinfunction "I1_10") (pintype "input"))
      (node (ref "E18") (pin "11") (pinfunction "O_11") (pintype "output"))
    )
    (net (code "93") (name "Net-(Q1-PadB)") (class "Default")
      (node (ref "Q1") (pin "B") (pinfunction "B_B") (pintype "passive"))
      (node (ref "R5") (pin "1") (pinfunction "1_1") (pintype "passive"))
    )
    (net (code "94") (name "Net-(Q1-PadE)") (class "Default")
      (node (ref "Q1") (pin "E") (pinfunction "E_E") (pintype "passive"))
      (node (ref "Q2") (pin "E") (pinfunction "E_E") (pintype "passive"))
      (node (ref "R6") (pin "2") (pinfunction "2_2") (pintype "passive"))
    )
    (net (code "95") (name "Net-(Q2-PadC)") (class "Default")
      (node (ref "Q2") (pin "C") (pinfunction "C_C") (pintype "passive"))
      (node (ref "Q3") (pin "B") (pinfunction "B_B") (pintype "passive"))
      (node (ref "R7") (pin "1") (pinfunction "1_1") (pintype "passive"))
    )
    (net (code "96") (name "Net-(Q3-PadC)") (class "Default")
      (node (ref "Q3") (pin "C") (pinfunction "C_C") (pintype "passive"))
      (node (ref "R9") (pin "1") (pinfunction "1_1") (pintype "passive"))
    )
    (net (code "97") (name "VCC") (class "Default")
      (node (ref "C1") (pin "1") (pinfunction "1_1") (pintype "passive"))
      (node (ref "C10") (pin "1") (pinfunction "1_1") (pintype "passive"))
      (node (ref "C11") (pin "1") (pinfunction "1_1") (pintype "passive"))
      (node (ref "C12") (pin "1") (pinfunction "1_1") (pintype "passive"))
      (node (ref "C13") (pin "1") (pinfunction "1_1") (pintype "passive"))
      (node (ref "C14") (pin "1") (pinfunction "1_1") (pintype "passive"))
      (node (ref "C15") (pin "1") (pinfunction "1_1") (pintype "passive"))
      (node (ref "C16") (pin "1") (pinfunction "1_1") (pintype "passive"))
      (node (ref "C17") (pin "1") (pinfunction "1_1") (pintype "passive"))
      (node (ref "C18") (pin "1") (pinfunction "1_1") (pintype "passive"))
      (node (ref "C2") (pin "1") (pinfunction "1_1") (pintype "passive"))
      (node (ref "C20") (pin "1") (pinfunction "1_1") (pintype "passive"))
      (node (ref "C21") (pin "+") (pinfunction "+_+") (pintype "passive"))
      (node (ref "C23") (pin "1") (pinfunction "1_1") (pintype "passive"))
      (node (ref "C3") (pin "1") (pinfunction "1_1") (pintype "passive"))
      (node (ref "C4") (pin "1") (pinfunction "1_1") (pintype "passive"))
      (node (ref "C5") (pin "1") (pinfunction "1_1") (pintype "passive"))
      (node (ref "C6") (pin "1") (pinfunction "1_1") (pintype "passive"))
      (node (ref "C7") (pin "1") (pinfunction "1_1") (pintype "passive"))
      (node (ref "C8") (pin "1") (pinfunction "1_1") (pintype "passive"))
      (node (ref "C9") (pin "1") (pinfunction "1_1") (pintype "passive"))
      (node (ref "Q1") (pin "C") (pinfunction "C_C") (pintype "passive"))
      (node (ref "Q3") (pin "E") (pinfunction "E_E") (pintype "passive"))
      (node (ref "R2") (pin "2") (pinfunction "2_2") (pintype "passive"))
      (node (ref "R3") (pin "2") (pinfunction "2_2") (pintype "passive"))
      (node (ref "R7") (pin "2") (pinfunction "2_2") (pintype "passive"))
      (node (ref "R8") (pin "1") (pinfunction "1_1") (pintype "passive"))
      (node (ref "U$2") (pin "AA2") (pinfunction "1_AA2") (pintype "bidirectional"))
      (node (ref "U$2") (pin "BA2") (pinfunction "1_BA2") (pintype "bidirectional"))
    )
    (net (code "98") (name "unconnected-(E6B-~{Q}-Pad8)") (class "Default")
      (node (ref "E6") (pin "8") (pinfunction "~{Q}_8") (pintype "output"))
    )
    (net (code "99") (name "unconnected-(E16A-Q-Pad5)") (class "Default")
      (node (ref "E16") (pin "5") (pinfunction "Q_5") (pintype "output"))
    )
    (net (code "100") (name "unconnected-(E18A-O-Pad3)") (class "Default")
      (node (ref "E18") (pin "3") (pinfunction "O_3") (pintype "output"))
    )
    (net (code "101") (name "unconnected-(E18B-O-Pad6)") (class "Default")
      (node (ref "E18") (pin "6") (pinfunction "O_6") (pintype "output"))
    )
  )
)
